# Memory.net
KiCad netlist of a schematic drawn in Altium Designer
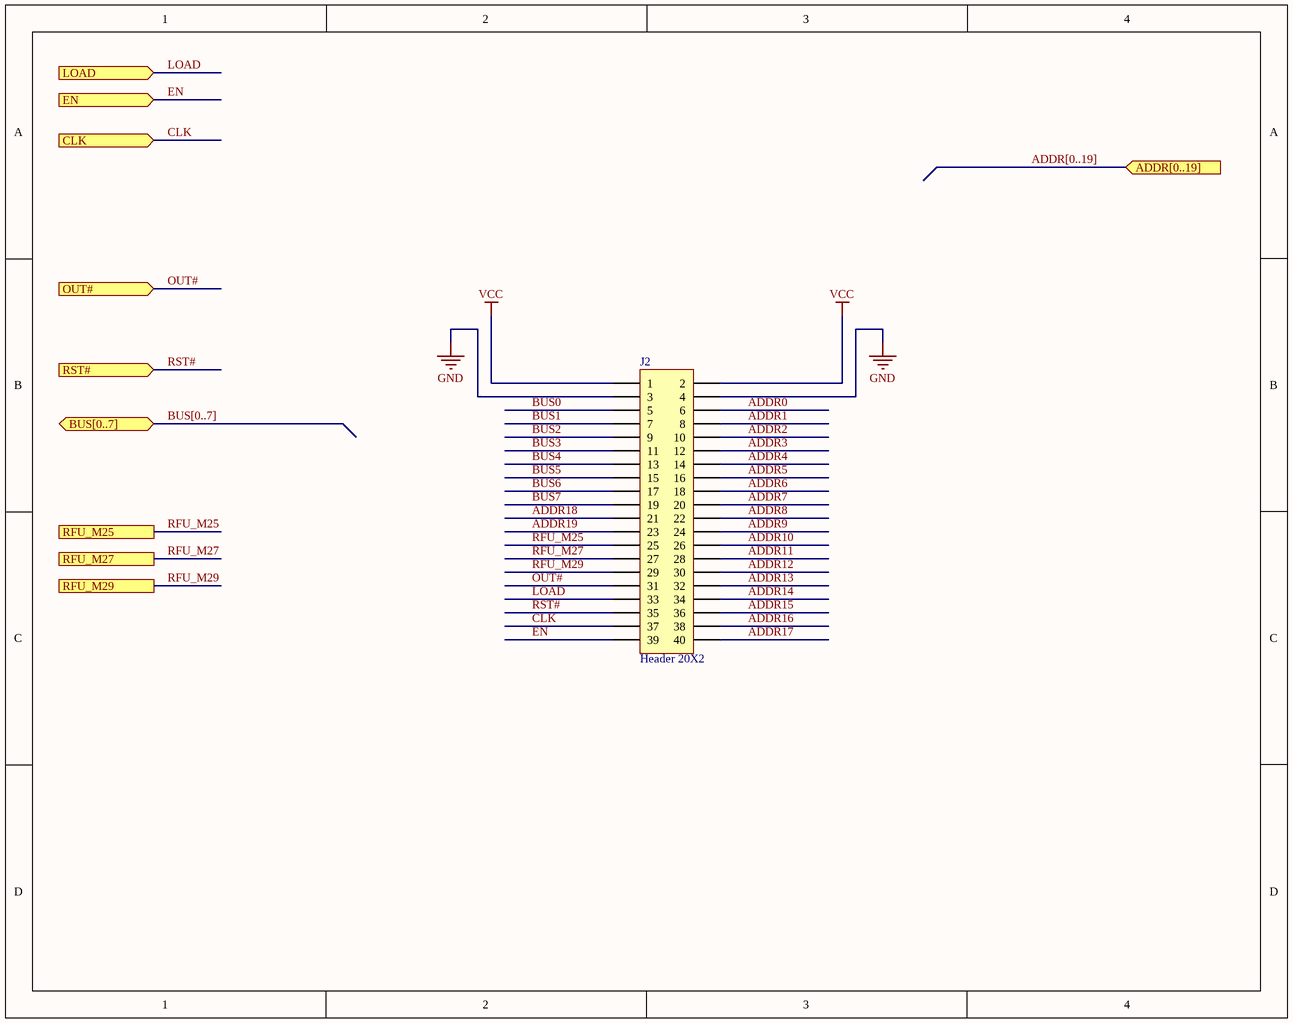
[diagram p0: Memory.SchDoc]

(export (version "E")
  (design (tool "Eeschema 10.0.6"))
  (components
    (comp (ref "J2")
      (value "Header 20X2")
      (footprint "HDR2X20")
      (description "Header, 20-Pin, Dual row")
      (fields (field (name "PUBLISHER") "Altium Limited"))
      (libsource (lib "Miscellaneous Connectors") (part "Header 20X2"))
    )
  )
  (nets
    (net (code "1") (name "/ADDR0") (class "Default")
      (node (ref "J2") (pin "6") (pinfunction "6_6") (pintype "passive"))
    )
    (net (code "2") (name "/ADDR1") (class "Default")
      (node (ref "J2") (pin "8") (pinfunction "8_8") (pintype "passive"))
    )
    (net (code "3") (name "/ADDR2") (class "Default")
      (node (ref "J2") (pin "10") (pinfunction "10_10") (pintype "passive"))
    )
    (net (code "4") (name "/ADDR3") (class "Default")
      (node (ref "J2") (pin "12") (pinfunction "12_12") (pintype "passive"))
    )
    (net (code "5") (name "/ADDR4") (class "Default")
      (node (ref "J2") (pin "14") (pinfunction "14_14") (pintype "passive"))
    )
    (net (code "6") (name "/ADDR5") (class "Default")
      (node (ref "J2") (pin "16") (pinfunction "16_16") (pintype "passive"))
    )
    (net (code "7") (name "/ADDR6") (class "Default")
      (node (ref "J2") (pin "18") (pinfunction "18_18") (pintype "passive"))
    )
    (net (code "8") (name "/ADDR7") (class "Default")
      (node (ref "J2") (pin "20") (pinfunction "20_20") (pintype "passive"))
    )
    (net (code "9") (name "/ADDR8") (class "Default")
      (node (ref "J2") (pin "22") (pinfunction "22_22") (pintype "passive"))
    )
    (net (code "10") (name "/ADDR9") (class "Default")
      (node (ref "J2") (pin "24") (pinfunction "24_24") (pintype "passive"))
    )
    (net (code "11") (name "/ADDR10") (class "Default")
      (node (ref "J2") (pin "26") (pinfunction "26_26") (pintype "passive"))
    )
    (net (code "12") (name "/ADDR11") (class "Default")
      (node (ref "J2") (pin "28") (pinfunction "28_28") (pintype "passive"))
    )
    (net (code "13") (name "/ADDR12") (class "Default")
      (node (ref "J2") (pin "30") (pinfunction "30_30") (pintype "passive"))
    )
    (net (code "14") (name "/ADDR13") (class "Default")
      (node (ref "J2") (pin "32") (pinfunction "32_32") (pintype "passive"))
    )
    (net (code "15") (name "/ADDR14") (class "Default")
      (node (ref "J2") (pin "34") (pinfunction "34_34") (pintype "passive"))
    )
    (net (code "16") (name "/ADDR15") (class "Default")
      (node (ref "J2") (pin "36") (pinfunction "36_36") (pintype "passive"))
    )
    (net (code "17") (name "/ADDR16") (class "Default")
      (node (ref "J2") (pin "38") (pinfunction "38_38") (pintype "passive"))
    )
    (net (code "18") (name "/ADDR17") (class "Default")
      (node (ref "J2") (pin "40") (pinfunction "40_40") (pintype "passive"))
    )
    (net (code "19") (name "/ADDR18") (class "Default")
      (node (ref "J2") (pin "21") (pinfunction "21_21") (pintype "passive"))
    )
    (net (code "20") (name "/ADDR19") (class "Default")
      (node (ref "J2") (pin "23") (pinfunction "23_23") (pintype "passive"))
    )
    (net (code "22") (name "/BUS0") (class "Default")
      (node (ref "J2") (pin "5") (pinfunction "5_5") (pintype "passive"))
    )
    (net (code "23") (name "/BUS1") (class "Default")
      (node (ref "J2") (pin "7") (pinfunction "7_7") (pintype "passive"))
    )
    (net (code "24") (name "/BUS2") (class "Default")
      (node (ref "J2") (pin "9") (pinfunction "9_9") (pintype "passive"))
    )
    (net (code "25") (name "/BUS3") (class "Default")
      (node (ref "J2") (pin "11") (pinfunction "11_11") (pintype "passive"))
    )
    (net (code "26") (name "/BUS4") (class "Default")
      (node (ref "J2") (pin "13") (pinfunction "13_13") (pintype "passive"))
    )
    (net (code "27") (name "/BUS5") (class "Default")
      (node (ref "J2") (pin "15") (pinfunction "15_15") (pintype "passive"))
    )
    (net (code "28") (name "/BUS6") (class "Default")
      (node (ref "J2") (pin "17") (pinfunction "17_17") (pintype "passive"))
    )
    (net (code "29") (name "/BUS7") (class "Default")
      (node (ref "J2") (pin "19") (pinfunction "19_19") (pintype "passive"))
    )
    (net (code "31") (name "/CLK") (class "Default")
      (node (ref "J2") (pin "37") (pinfunction "37_37") (pintype "passive"))
    )
    (net (code "32") (name "/EN") (class "Default")
      (node (ref "J2") (pin "39") (pinfunction "39_39") (pintype "passive"))
    )
    (net (code "33") (name "/LOAD") (class "Default")
      (node (ref "J2") (pin "33") (pinfunction "33_33") (pintype "passive"))
    )
    (net (code "34") (name "/OUT#") (class "Default")
      (node (ref "J2") (pin "31") (pinfunction "31_31") (pintype "passive"))
    )
    (net (code "35") (name "/RFU_M25") (class "Default")
      (node (ref "J2") (pin "25") (pinfunction "25_25") (pintype "passive"))
    )
    (net (code "36") (name "/RFU_M27") (class "Default")
      (node (ref "J2") (pin "27") (pinfunction "27_27") (pintype "passive"))
    )
    (net (code "37") (name "/RFU_M29") (class "Default")
      (node (ref "J2") (pin "29") (pinfunction "29_29") (pintype "passive"))
    )
    (net (code "38") (name "/RST#") (class "Default")
      (node (ref "J2") (pin "35") (pinfunction "35_35") (pintype "passive"))
    )
    (net (code "39") (name "GND") (class "Default")
      (node (ref "J2") (pin "3") (pinfunction "3_3") (pintype "passive"))
      (node (ref "J2") (pin "4") (pinfunction "4_4") (pintype "passive"))
    )
    (net (code "40") (name "VCC") (class "Default")
      (node (ref "J2") (pin "1") (pinfunction "1_1") (pintype "passive"))
      (node (ref "J2") (pin "2") (pinfunction "2_2") (pintype "passive"))
    )
  )
)
